# cny70.net
KiCad netlist of a schematic drawn in EAGLE
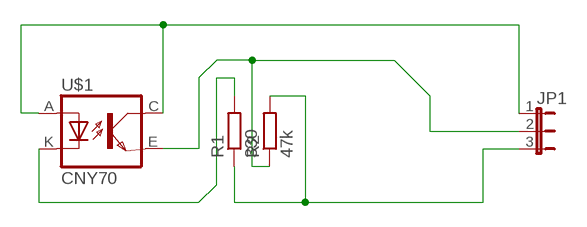
[diagram p0: schematic, sheet 1]

(export (version "E")
  (design (tool "Eeschema 10.0.6"))
  (components
    (comp (ref "JP1")
      (value "JP2E")
      (footprint "eagle-import:JP2")
      (libsource (lib "eagle-import") (part "JP2E"))
    )
    (comp (ref "R1")
      (value "330")
      (footprint "eagle-import:0207_10")
      (libsource (lib "eagle-import") (part "R-EU_0207/10"))
    )
    (comp (ref "R2")
      (value "47k")
      (footprint "eagle-import:0207_10")
      (libsource (lib "eagle-import") (part "R-EU_0207/10"))
    )
    (comp (ref "U$1")
      (value "CNY70")
      (footprint "eagle-import:4")
      (libsource (lib "eagle-import") (part "CNY70"))
    )
  )
  (nets
    (net (code "1") (name "Net-(JP1-Pad3)") (class "Default")
      (node (ref "JP1") (pin "3") (pinfunction "3_3") (pintype "passive"))
      (node (ref "R1") (pin "1") (pinfunction "1_1") (pintype "passive"))
      (node (ref "R2") (pin "2") (pinfunction "2_2") (pintype "passive"))
    )
    (net (code "2") (name "Net-(U$1-C)") (class "Default")
      (node (ref "R1") (pin "2") (pinfunction "2_2") (pintype "passive"))
      (node (ref "U$1") (pin "K") (pinfunction "C_K") (pintype "passive"))
    )
    (net (code "3") (name "Net-(U$1-COL)") (class "Default")
      (node (ref "JP1") (pin "1") (pinfunction "1_1") (pintype "passive"))
      (node (ref "U$1") (pin "A") (pinfunction "A_A") (pintype "passive"))
      (node (ref "U$1") (pin "C") (pinfunction "COL_C") (pintype "passive"))
    )
    (net (code "4") (name "Net-(U$1-EMI)") (class "Default")
      (node (ref "JP1") (pin "2") (pinfunction "2_2") (pintype "passive"))
      (node (ref "R2") (pin "1") (pinfunction "1_1") (pintype "passive"))
      (node (ref "U$1") (pin "E") (pinfunction "EMI_E") (pintype "passive"))
    )
  )
)
